# TLog_HighSpeedADC.net
KiCad netlist of a schematic drawn in EAGLE
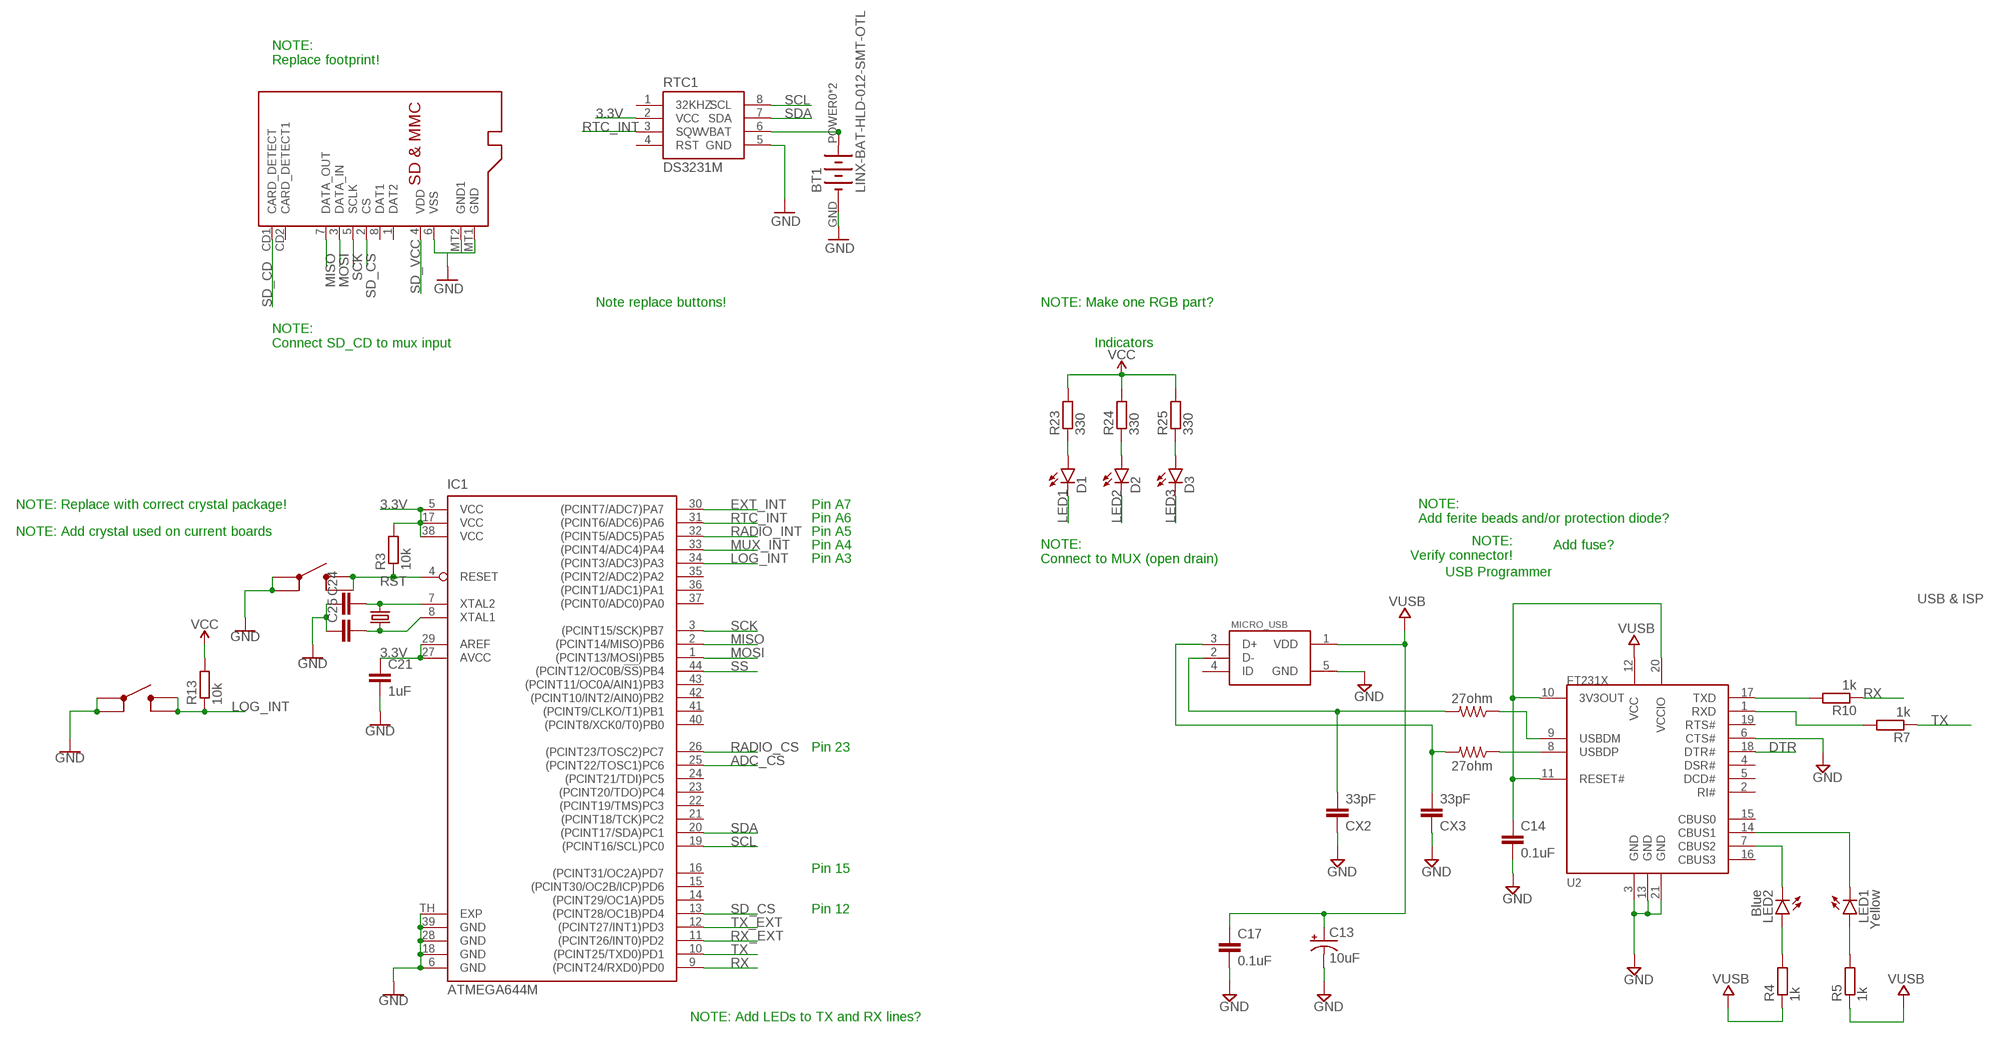
[diagram p0: schematic, sheet 1]
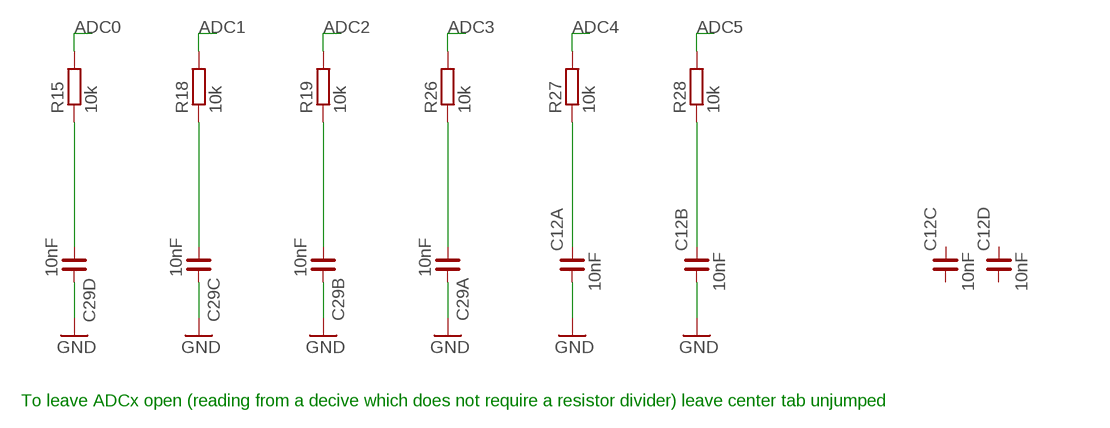
[diagram p1: schematic, sheet 2]
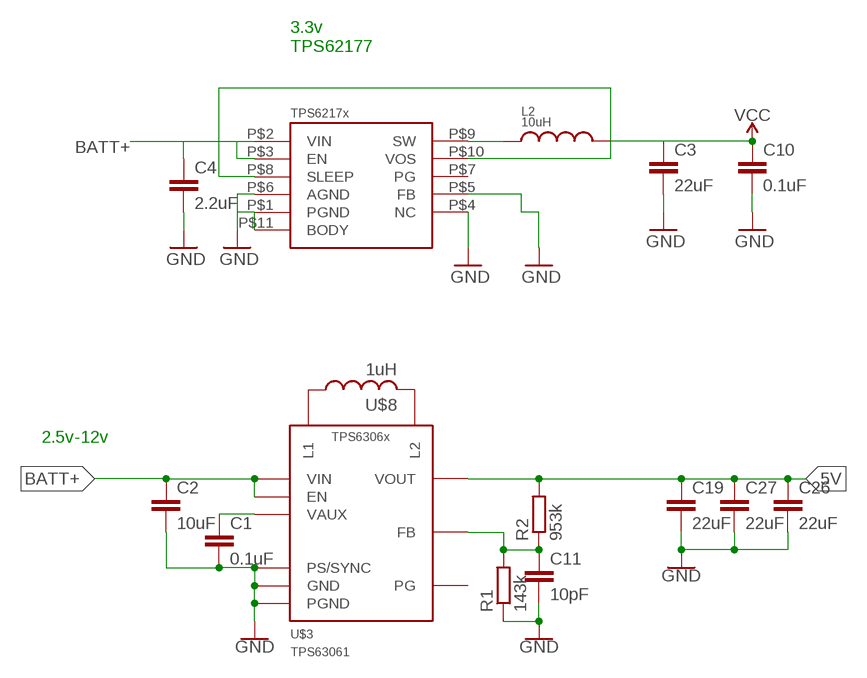
[diagram p2: schematic, sheet 3]
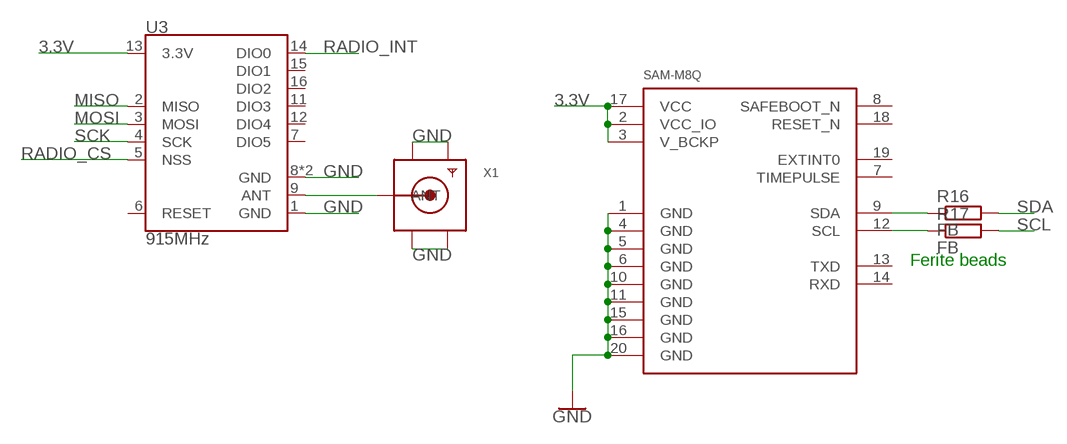
[diagram p3: schematic, sheet 4]
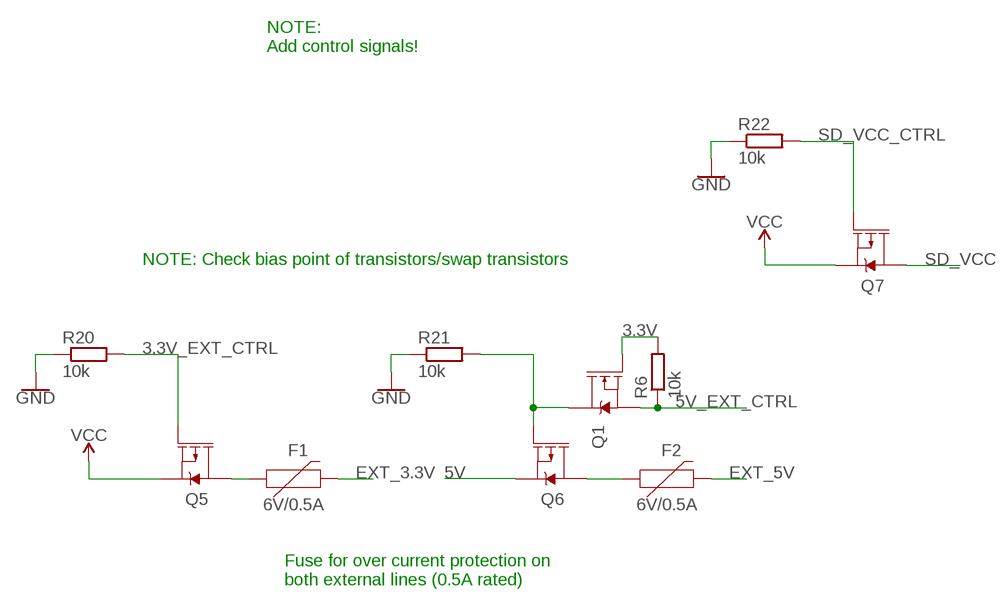
[diagram p4: schematic, sheet 5]
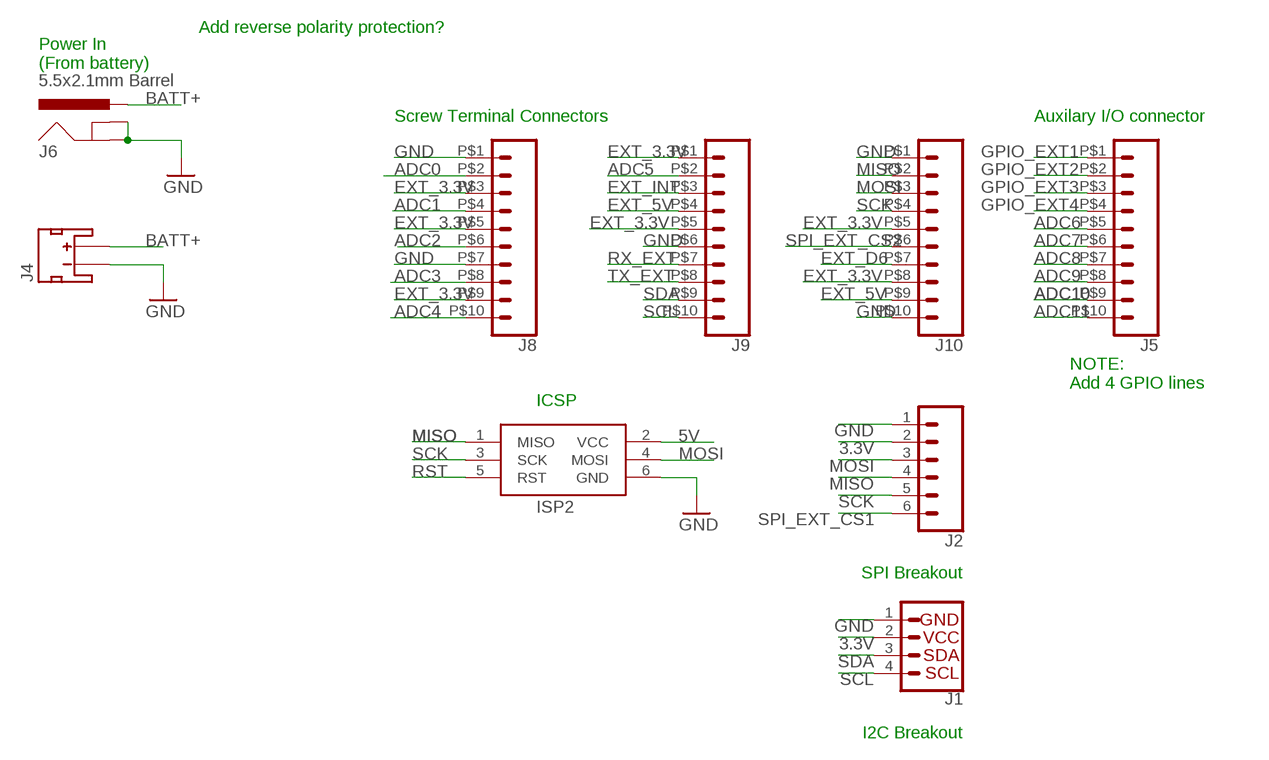
[diagram p5: schematic, sheet 6]
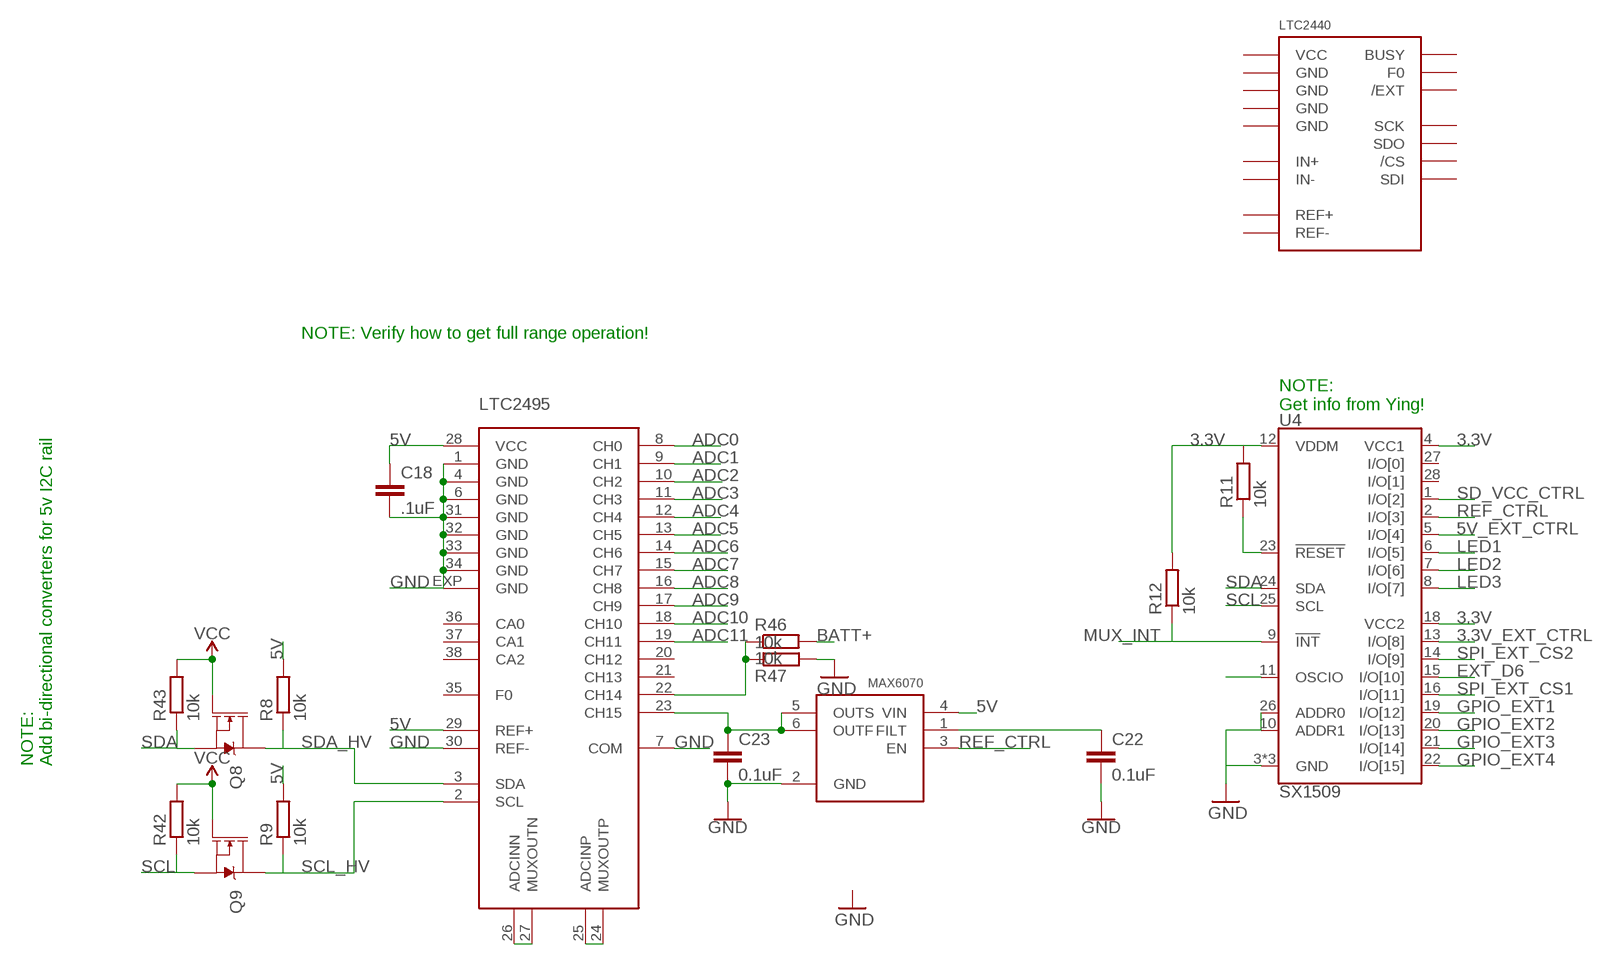
[diagram p6: schematic, sheet 7]

(export (version "E")
  (design (tool "Eeschema 10.0.6"))
  (components
    (comp (ref "R16")
      (value "FB")
      (footprint "eagle-import:R0603")
      (libsource (lib "eagle-import") (part "R-EU_R0603"))
    )
    (comp (ref "R17")
      (value "FB")
      (footprint "eagle-import:R0603")
      (libsource (lib "eagle-import") (part "R-EU_R0603"))
    )
    (comp (ref "U$6")
      (value "SAM-M8Q")
      (footprint "eagle-import:SAM-M8Q")
      (libsource (lib "eagle-import") (part "SAM-M8Q"))
    )
    (comp (ref "U3")
      (value "915MHz")
      (footprint "eagle-import:RFM69HCW-XXXS2")
      (libsource (lib "eagle-import") (part "RFM69HCW-915"))
    )
    (comp (ref "X1")
      (value "SMACONNECTOR_EDGE")
      (footprint "eagle-import:SMA_EDGELAUNCH")
      (libsource (lib "eagle-import") (part "SMACONNECTOR_EDGE"))
    )
    (comp (ref "C12")
      (value "10nF")
      (footprint "eagle-import:CECJ-1206")
      (libsource (lib "eagle-import") (part "CCA_ECJ-1206"))
    )
    (comp (ref "C29")
      (value "10nF")
      (footprint "eagle-import:CECJ-1206")
      (libsource (lib "eagle-import") (part "CCA_ECJ-1206"))
    )
    (comp (ref "R15")
      (value "10k")
      (footprint "eagle-import:R0603")
      (libsource (lib "eagle-import") (part "R-EU_R0603"))
    )
    (comp (ref "R18")
      (value "10k")
      (footprint "eagle-import:R0603")
      (libsource (lib "eagle-import") (part "R-EU_R0603"))
    )
    (comp (ref "R19")
      (value "10k")
      (footprint "eagle-import:R0603")
      (libsource (lib "eagle-import") (part "R-EU_R0603"))
    )
    (comp (ref "R26")
      (value "10k")
      (footprint "eagle-import:R0603")
      (libsource (lib "eagle-import") (part "R-EU_R0603"))
    )
    (comp (ref "R27")
      (value "10k")
      (footprint "eagle-import:R0603")
      (libsource (lib "eagle-import") (part "R-EU_R0603"))
    )
    (comp (ref "R28")
      (value "10k")
      (footprint "eagle-import:R0603")
      (libsource (lib "eagle-import") (part "R-EU_R0603"))
    )
    (comp (ref "C18")
      (value ".1uF")
      (footprint "eagle-import:C0603")
      (libsource (lib "eagle-import") (part "C-EUC0603"))
    )
    (comp (ref "C22")
      (value "0.1uF")
      (footprint "eagle-import:C0603")
      (libsource (lib "eagle-import") (part "C-EUC0603"))
    )
    (comp (ref "C23")
      (value "0.1uF")
      (footprint "eagle-import:C0603")
      (libsource (lib "eagle-import") (part "C-EUC0603"))
    )
    (comp (ref "Q8")
      (value "220mA/50V/3.5Ω")
      (footprint "eagle-import:SOT23-3")
      (libsource (lib "eagle-import") (part "MOSFET-NCH-BSS138"))
    )
    (comp (ref "Q9")
      (value "220mA/50V/3.5Ω")
      (footprint "eagle-import:SOT23-3")
      (libsource (lib "eagle-import") (part "MOSFET-NCH-BSS138"))
    )
    (comp (ref "R8")
      (value "10k")
      (footprint "eagle-import:R0603")
      (libsource (lib "eagle-import") (part "R-EU_R0603"))
    )
    (comp (ref "R9")
      (value "10k")
      (footprint "eagle-import:R0603")
      (libsource (lib "eagle-import") (part "R-EU_R0603"))
    )
    (comp (ref "R11")
      (value "10k")
      (footprint "eagle-import:R0603")
      (libsource (lib "eagle-import") (part "R-EU_R0603"))
    )
    (comp (ref "R12")
      (value "10k")
      (footprint "eagle-import:R0603")
      (libsource (lib "eagle-import") (part "R-EU_R0603"))
    )
    (comp (ref "R42")
      (value "10k")
      (footprint "eagle-import:R0603")
      (libsource (lib "eagle-import") (part "R-EU_R0603"))
    )
    (comp (ref "R43")
      (value "10k")
      (footprint "eagle-import:R0603")
      (libsource (lib "eagle-import") (part "R-EU_R0603"))
    )
    (comp (ref "R46")
      (value "10k")
      (footprint "eagle-import:R0603")
      (libsource (lib "eagle-import") (part "R-EU_R0603"))
    )
    (comp (ref "R47")
      (value "10k")
      (footprint "eagle-import:R0603")
      (libsource (lib "eagle-import") (part "R-EU_R0603"))
    )
    (comp (ref "U$7")
      (value "LTC2495")
      (footprint "eagle-import:QFN38-5X7")
      (libsource (lib "eagle-import") (part "LTC2495"))
    )
    (comp (ref "U$10")
      (value "MAX6070")
      (footprint "eagle-import:SOT23-6L")
      (libsource (lib "eagle-import") (part "MAX6070"))
    )
    (comp (ref "U$15")
      (value "LTC2440")
      (footprint "eagle-import:SSOP16")
      (libsource (lib "eagle-import") (part "LTC2440"))
    )
    (comp (ref "U4")
      (value "SX1509")
      (footprint "eagle-import:QFN-28")
      (libsource (lib "eagle-import") (part "SX1509"))
    )
    (comp (ref "BT1")
      (value "LINX-BAT-HLD-012-SMT-OTL")
      (footprint "eagle-import:LINX_BAT-HLD-012-SMT")
      (libsource (lib "eagle-import") (part "LINX-BAT-HLD-012-SMT-OTL"))
    )
    (comp (ref "C13")
      (value "10uF")
      (footprint "eagle-import:EIA3216")
      (libsource (lib "eagle-import") (part "CAP_POL1206"))
    )
    (comp (ref "C14")
      (value "0.1uF")
      (footprint "eagle-import:C0603")
      (libsource (lib "eagle-import") (part "resistor_C-EUC0603"))
    )
    (comp (ref "C17")
      (value "0.1uF")
      (footprint "eagle-import:C0603")
      (libsource (lib "eagle-import") (part "resistor_C-EUC0603"))
    )
    (comp (ref "C21")
      (value "1uF")
      (footprint "eagle-import:C0603")
      (libsource (lib "eagle-import") (part "C-EUC0603"))
    )
    (comp (ref "C24")
      (value "C-EUC0603")
      (footprint "eagle-import:C0603")
      (libsource (lib "eagle-import") (part "C-EUC0603"))
    )
    (comp (ref "C25")
      (value "C-EUC0603")
      (footprint "eagle-import:C0603")
      (libsource (lib "eagle-import") (part "C-EUC0603"))
    )
    (comp (ref "CX2")
      (value "33pF")
      (footprint "eagle-import:C0603")
      (libsource (lib "eagle-import") (part "resistor_C-EUC0603"))
    )
    (comp (ref "CX3")
      (value "33pF")
      (footprint "eagle-import:C0603")
      (libsource (lib "eagle-import") (part "resistor_C-EUC0603"))
    )
    (comp (ref "D+")
      (value "27ohm")
      (footprint "eagle-import:R0603")
      (libsource (lib "eagle-import") (part "R-US_R0603"))
    )
    (comp (ref "D-")
      (value "27ohm")
      (footprint "eagle-import:R0603")
      (libsource (lib "eagle-import") (part "R-US_R0603"))
    )
    (comp (ref "D1")
      (value "LED0603")
      (footprint "eagle-import:LED-0603")
      (libsource (lib "eagle-import") (part "LED0603"))
    )
    (comp (ref "D2")
      (value "LED0603")
      (footprint "eagle-import:LED-0603")
      (libsource (lib "eagle-import") (part "LED0603"))
    )
    (comp (ref "D3")
      (value "LED0603")
      (footprint "eagle-import:LED-0603")
      (libsource (lib "eagle-import") (part "LED0603"))
    )
    (comp (ref "IC1")
      (value "ATMEGA644M")
      (footprint "eagle-import:MLF44-TH")
      (fields (field (name "MPN") "ATMEGA644P-20MU"))
      (libsource (lib "eagle-import") (part "ATMEGA644M"))
    )
    (comp (ref "LED1")
      (value "Yellow")
      (footprint "eagle-import:LED-0603")
      (libsource (lib "eagle-import") (part "LED0603"))
    )
    (comp (ref "LED2")
      (value "Blue")
      (footprint "eagle-import:LED-0603")
      (libsource (lib "eagle-import") (part "LED0603"))
    )
    (comp (ref "MICRO_USB")
      (value "10118194-0001LF_LONGER_PADS")
      (footprint "eagle-import:10118194-0001LF_LONGER_PADS")
      (libsource (lib "eagle-import") (part "10118194-0001LF_LONGER_PADS"))
    )
    (comp (ref "R3")
      (value "10k")
      (footprint "eagle-import:R0603")
      (libsource (lib "eagle-import") (part "R-EU_R0603"))
    )
    (comp (ref "R4")
      (value "1k")
      (footprint "eagle-import:R0603")
      (libsource (lib "eagle-import") (part "rcl_334_R-EU_R0603"))
    )
    (comp (ref "R5")
      (value "1k")
      (footprint "eagle-import:R0603")
      (libsource (lib "eagle-import") (part "rcl_334_R-EU_R0603"))
    )
    (comp (ref "R7")
      (value "1k")
      (footprint "eagle-import:R0603")
      (libsource (lib "eagle-import") (part "rcl_334_R-EU_R0603"))
    )
    (comp (ref "R10")
      (value "1k")
      (footprint "eagle-import:R0603")
      (libsource (lib "eagle-import") (part "rcl_334_R-EU_R0603"))
    )
    (comp (ref "R13")
      (value "10k")
      (footprint "eagle-import:R0603")
      (libsource (lib "eagle-import") (part "resistor_R-EU_R0603"))
    )
    (comp (ref "R23")
      (value "330")
      (footprint "eagle-import:R0603")
      (libsource (lib "eagle-import") (part "R-EU_R0603"))
    )
    (comp (ref "R24")
      (value "330")
      (footprint "eagle-import:R0603")
      (libsource (lib "eagle-import") (part "R-EU_R0603"))
    )
    (comp (ref "R25")
      (value "330")
      (footprint "eagle-import:R0603")
      (libsource (lib "eagle-import") (part "R-EU_R0603"))
    )
    (comp (ref "RTC1")
      (value "DS3231M")
      (footprint "eagle-import:SO08")
      (libsource (lib "eagle-import") (part "DS3231M"))
    )
    (comp (ref "U$1")
      (value "CRYSTAL_5X3.2_2LEAD")
      (footprint "eagle-import:CRYSTAL_5X3.2_2-SMD")
      (libsource (lib "eagle-import") (part "CRYSTAL_5X3.2_2LEAD"))
    )
    (comp (ref "U$2")
      (value "MICROSD")
      (footprint "eagle-import:MICROSD")
      (libsource (lib "eagle-import") (part "MICROSD"))
    )
    (comp (ref "U$5")
      (value "SKRPABE010")
      (footprint "eagle-import:SKRPABE010_(SWITCH)")
      (libsource (lib "eagle-import") (part "SKRPABE010"))
    )
    (comp (ref "U$9")
      (value "SKRPABE010")
      (footprint "eagle-import:SKRPABE010_(SWITCH)")
      (libsource (lib "eagle-import") (part "SKRPABE010"))
    )
    (comp (ref "U2")
      (value "FT231X-Q")
      (footprint "eagle-import:QFN20")
      (libsource (lib "eagle-import") (part "FT231X-Q"))
    )
    (comp (ref "F1")
      (value "6V/0.5A")
      (footprint "eagle-import:1206")
      (libsource (lib "eagle-import") (part "PPTC_HALF-AMP"))
    )
    (comp (ref "F2")
      (value "6V/0.5A")
      (footprint "eagle-import:1206")
      (libsource (lib "eagle-import") (part "PPTC_HALF-AMP"))
    )
    (comp (ref "Q1")
      (value "220mA/50V/3.5Ω")
      (footprint "eagle-import:SOT23-3")
      (libsource (lib "eagle-import") (part "MOSFET-NCH-BSS138"))
    )
    (comp (ref "Q5")
      (value "4.3A/20V/54mΩ")
      (footprint "eagle-import:SOT23-3")
      (libsource (lib "eagle-import") (part "MOSFET_PCH-IRLML2244"))
    )
    (comp (ref "Q6")
      (value "4.3A/20V/54mΩ")
      (footprint "eagle-import:SOT23-3")
      (libsource (lib "eagle-import") (part "MOSFET_PCH-IRLML2244"))
    )
    (comp (ref "Q7")
      (value "4.3A/20V/54mΩ")
      (footprint "eagle-import:SOT23-3")
      (libsource (lib "eagle-import") (part "MOSFET_PCH-IRLML2244"))
    )
    (comp (ref "R6")
      (value "10k")
      (footprint "eagle-import:R0603")
      (libsource (lib "eagle-import") (part "resistor_R-EU_R0603"))
    )
    (comp (ref "R20")
      (value "10k")
      (footprint "eagle-import:R0603")
      (libsource (lib "eagle-import") (part "R-EU_R0603"))
    )
    (comp (ref "R21")
      (value "10k")
      (footprint "eagle-import:R0603")
      (libsource (lib "eagle-import") (part "R-EU_R0603"))
    )
    (comp (ref "R22")
      (value "10k")
      (footprint "eagle-import:R0603")
      (libsource (lib "eagle-import") (part "R-EU_R0603"))
    )
    (comp (ref "C1")
      (value "0.1uF")
      (footprint "eagle-import:C0603")
      (libsource (lib "eagle-import") (part "C-EUC0603"))
    )
    (comp (ref "C2")
      (value "10uF")
      (footprint "eagle-import:C0603")
      (libsource (lib "eagle-import") (part "C-EUC0603"))
    )
    (comp (ref "C3")
      (value "22uF")
      (footprint "eagle-import:C1210")
      (libsource (lib "eagle-import") (part "C-EUC1210"))
    )
    (comp (ref "C4")
      (value "2.2uF")
      (footprint "eagle-import:C0603")
      (libsource (lib "eagle-import") (part "C-EUC0603"))
    )
    (comp (ref "C10")
      (value "0.1uF")
      (footprint "eagle-import:C0603")
      (libsource (lib "eagle-import") (part "C-EUC0603"))
    )
    (comp (ref "C11")
      (value "10pF")
      (footprint "eagle-import:C0603")
      (libsource (lib "eagle-import") (part "C-EUC0603"))
    )
    (comp (ref "C19")
      (value "22uF")
      (footprint "eagle-import:C0603")
      (libsource (lib "eagle-import") (part "C-EUC0603"))
    )
    (comp (ref "C26")
      (value "22uF")
      (footprint "eagle-import:C0603")
      (libsource (lib "eagle-import") (part "C-EUC0603"))
    )
    (comp (ref "C27")
      (value "22uF")
      (footprint "eagle-import:C0603")
      (libsource (lib "eagle-import") (part "C-EUC0603"))
    )
    (comp (ref "L2")
      (value "10uH")
      (footprint "eagle-import:WE-LQS(INDUCTOR)")
      (libsource (lib "eagle-import") (part "WE-LSQ(INDUCTOR)"))
    )
    (comp (ref "R1")
      (value "143k")
      (footprint "eagle-import:R0603")
      (libsource (lib "eagle-import") (part "R-EU_R0603"))
    )
    (comp (ref "R2")
      (value "953k")
      (footprint "eagle-import:R0603")
      (libsource (lib "eagle-import") (part "R-EU_R0603"))
    )
    (comp (ref "U$3")
      (value "TPS63061")
      (footprint "eagle-import:WSON-10")
      (libsource (lib "eagle-import") (part "TPS306X"))
    )
    (comp (ref "U$4")
      (value "TPS6217X")
      (footprint "eagle-import:WSON-10")
      (libsource (lib "eagle-import") (part "TPS6217X"))
    )
    (comp (ref "U$8")
      (value "1uH")
      (footprint "eagle-import:WE-MAIA(4.1X4.1)")
      (libsource (lib "eagle-import") (part "WE-MAIA(INDUCTOR)"))
    )
    (comp (ref "ISP2")
      (value "AVRISP-6")
      (footprint "eagle-import:AVRISP")
      (libsource (lib "eagle-import") (part "AVRISP-6"))
    )
    (comp (ref "J1")
      (value "I2C_STANDARD")
      (footprint "eagle-import:1X04")
      (libsource (lib "eagle-import") (part "I2C_STANDARD"))
    )
    (comp (ref "J2")
      (value "CONN_06SILK_FEMALE_PTH")
      (footprint "eagle-import:1X06")
      (libsource (lib "eagle-import") (part "CONN_06SILK_FEMALE_PTH"))
    )
    (comp (ref "J4")
      (value "JST_2MM_MALE")
      (footprint "eagle-import:JST-2-SMD")
      (libsource (lib "eagle-import") (part "JST_2MM_MALE"))
    )
    (comp (ref "J5")
      (value "CONN_10")
      (footprint "eagle-import:SCREWTERMINAL-3.5MM-10")
      (libsource (lib "eagle-import") (part "CONN_10"))
    )
    (comp (ref "J6")
      (value "5.5x2.1mm Barrel")
      (footprint "eagle-import:POWER_JACK_SMD")
      (libsource (lib "eagle-import") (part "POWER_JACKSMD"))
    )
    (comp (ref "J8")
      (value "CONN_10")
      (footprint "eagle-import:SCREWTERMINAL-3.5MM-10")
      (libsource (lib "eagle-import") (part "CONN_10"))
    )
    (comp (ref "J9")
      (value "CONN_10")
      (footprint "eagle-import:SCREWTERMINAL-3.5MM-10")
      (libsource (lib "eagle-import") (part "CONN_10"))
    )
    (comp (ref "J10")
      (value "CONN_10")
      (footprint "eagle-import:SCREWTERMINAL-3.5MM-10")
      (libsource (lib "eagle-import") (part "CONN_10"))
    )
  )
  (nets
    (net (code "1") (name "3.3V") (class "Default")
      (node (ref "C10") (pin "1") (pinfunction "1_1") (pintype "passive"))
      (node (ref "C21") (pin "1") (pinfunction "1_1") (pintype "passive"))
      (node (ref "C3") (pin "1") (pinfunction "1_1") (pintype "passive"))
      (node (ref "IC1") (pin "17") (pinfunction "VCC_17") (pintype "power_in"))
      (node (ref "IC1") (pin "27") (pinfunction "AVCC_27") (pintype "power_in"))
      (node (ref "IC1") (pin "29") (pinfunction "AREF_29") (pintype "passive"))
      (node (ref "IC1") (pin "38") (pinfunction "VCC_38") (pintype "power_in"))
      (node (ref "IC1") (pin "5") (pinfunction "VCC_5") (pintype "power_in"))
      (node (ref "J1") (pin "2") (pinfunction "2_2") (pintype "power_in"))
      (node (ref "J2") (pin "2") (pinfunction "2_2") (pintype "passive"))
      (node (ref "L2") (pin "P$2") (pinfunction "P$2_P$2") (pintype "bidirectional"))
      (node (ref "Q1") (pin "1") (pinfunction "G_1") (pintype "bidirectional"))
      (node (ref "Q5") (pin "2") (pinfunction "S_2") (pintype "bidirectional"))
      (node (ref "Q7") (pin "2") (pinfunction "S_2") (pintype "bidirectional"))
      (node (ref "Q8") (pin "1") (pinfunction "G_1") (pintype "bidirectional"))
      (node (ref "Q9") (pin "1") (pinfunction "G_1") (pintype "bidirectional"))
      (node (ref "R11") (pin "2") (pinfunction "2_2") (pintype "passive"))
      (node (ref "R12") (pin "2") (pinfunction "2_2") (pintype "passive"))
      (node (ref "R13") (pin "2") (pinfunction "2_2") (pintype "passive"))
      (node (ref "R23") (pin "2") (pinfunction "2_2") (pintype "passive"))
      (node (ref "R24") (pin "2") (pinfunction "2_2") (pintype "passive"))
      (node (ref "R25") (pin "2") (pinfunction "2_2") (pintype "passive"))
      (node (ref "R3") (pin "2") (pinfunction "2_2") (pintype "passive"))
      (node (ref "R42") (pin "2") (pinfunction "2_2") (pintype "passive"))
      (node (ref "R43") (pin "2") (pinfunction "2_2") (pintype "passive"))
      (node (ref "R6") (pin "2") (pinfunction "2_2") (pintype "passive"))
      (node (ref "RTC1") (pin "2") (pinfunction "VCC_2") (pintype "power_in"))
      (node (ref "U$4") (pin "P$10") (pinfunction "VOS_P$10") (pintype "bidirectional"))
      (node (ref "U$4") (pin "P$8") (pinfunction "SLEEP_P$8") (pintype "bidirectional"))
      (node (ref "U$6") (pin "17") (pinfunction "VCC_17") (pintype "bidirectional"))
      (node (ref "U$6") (pin "2") (pinfunction "VCC_IO_2") (pintype "bidirectional"))
      (node (ref "U$6") (pin "3") (pinfunction "V_BCKP_3") (pintype "bidirectional"))
      (node (ref "U3") (pin "13") (pinfunction "3.3V_13") (pintype "power_in"))
      (node (ref "U4") (pin "12") (pinfunction "VDDM_12") (pintype "bidirectional"))
      (node (ref "U4") (pin "18") (pinfunction "VCC2_18") (pintype "bidirectional"))
      (node (ref "U4") (pin "4") (pinfunction "VCC1_4") (pintype "bidirectional"))
    )
    (net (code "2") (name "3.3V_EXT_CTRL") (class "Default")
      (node (ref "Q5") (pin "1") (pinfunction "G_1") (pintype "bidirectional"))
      (node (ref "R20") (pin "2") (pinfunction "2_2") (pintype "passive"))
      (node (ref "U4") (pin "13") (pinfunction "I/O[8]_13") (pintype "bidirectional"))
    )
    (net (code "3") (name "5V") (class "Default")
      (node (ref "C18") (pin "1") (pinfunction "1_1") (pintype "passive"))
      (node (ref "C19") (pin "1") (pinfunction "1_1") (pintype "passive"))
      (node (ref "C26") (pin "1") (pinfunction "1_1") (pintype "passive"))
      (node (ref "C27") (pin "1") (pinfunction "1_1") (pintype "passive"))
      (node (ref "ISP2") (pin "2") (pinfunction "VCC_2") (pintype "power_in"))
      (node (ref "Q6") (pin "2") (pinfunction "S_2") (pintype "bidirectional"))
      (node (ref "R2") (pin "2") (pinfunction "2_2") (pintype "passive"))
      (node (ref "R8") (pin "2") (pinfunction "2_2") (pintype "passive"))
      (node (ref "R9") (pin "2") (pinfunction "2_2") (pintype "passive"))
      (node (ref "U$10") (pin "4") (pinfunction "VIN_4") (pintype "bidirectional"))
      (node (ref "U$3") (pin "P$9") (pinfunction "VOUT_P$9") (pintype "input"))
      (node (ref "U$7") (pin "28") (pinfunction "VCC_28") (pintype "power_in"))
      (node (ref "U$7") (pin "29") (pinfunction "REF+_29") (pintype "input"))
    )
    (net (code "4") (name "5V_EXT_CTRL") (class "Default")
      (node (ref "Q1") (pin "2") (pinfunction "S_2") (pintype "bidirectional"))
      (node (ref "R6") (pin "1") (pinfunction "1_1") (pintype "passive"))
      (node (ref "U4") (pin "5") (pinfunction "I/O[4]_5") (pintype "bidirectional"))
    )
    (net (code "5") (name "ADC0") (class "Default")
      (node (ref "J8") (pin "P$2") (pinfunction "2_P$2") (pintype "passive"))
      (node (ref "R15") (pin "2") (pinfunction "2_2") (pintype "passive"))
      (node (ref "U$7") (pin "8") (pinfunction "CH0_8") (pintype "input"))
    )
    (net (code "6") (name "ADC1") (class "Default")
      (node (ref "J8") (pin "P$4") (pinfunction "4_P$4") (pintype "passive"))
      (node (ref "R18") (pin "2") (pinfunction "2_2") (pintype "passive"))
      (node (ref "U$7") (pin "9") (pinfunction "CH1_9") (pintype "input"))
    )
    (net (code "7") (name "ADC2") (class "Default")
      (node (ref "J8") (pin "P$6") (pinfunction "6_P$6") (pintype "passive"))
      (node (ref "R19") (pin "2") (pinfunction "2_2") (pintype "passive"))
      (node (ref "U$7") (pin "10") (pinfunction "CH2_10") (pintype "input"))
    )
    (net (code "8") (name "ADC3") (class "Default")
      (node (ref "J8") (pin "P$8") (pinfunction "8_P$8") (pintype "passive"))
      (node (ref "R26") (pin "2") (pinfunction "2_2") (pintype "passive"))
      (node (ref "U$7") (pin "11") (pinfunction "CH3_11") (pintype "input"))
    )
    (net (code "9") (name "ADC4") (class "Default")
      (node (ref "J8") (pin "P$10") (pinfunction "10_P$10") (pintype "passive"))
      (node (ref "R27") (pin "2") (pinfunction "2_2") (pintype "passive"))
      (node (ref "U$7") (pin "12") (pinfunction "CH4_12") (pintype "input"))
    )
    (net (code "10") (name "ADC5") (class "Default")
      (node (ref "J9") (pin "P$2") (pinfunction "2_P$2") (pintype "passive"))
      (node (ref "R28") (pin "2") (pinfunction "2_2") (pintype "passive"))
      (node (ref "U$7") (pin "13") (pinfunction "CH5_13") (pintype "input"))
    )
    (net (code "11") (name "ADC6") (class "Default")
      (node (ref "J5") (pin "P$5") (pinfunction "5_P$5") (pintype "passive"))
      (node (ref "U$7") (pin "14") (pinfunction "CH6_14") (pintype "input"))
    )
    (net (code "12") (name "ADC7") (class "Default")
      (node (ref "J5") (pin "P$6") (pinfunction "6_P$6") (pintype "passive"))
      (node (ref "U$7") (pin "15") (pinfunction "CH7_15") (pintype "input"))
    )
    (net (code "13") (name "ADC8") (class "Default")
      (node (ref "J5") (pin "P$7") (pinfunction "7_P$7") (pintype "passive"))
      (node (ref "U$7") (pin "16") (pinfunction "CH8_16") (pintype "input"))
    )
    (net (code "14") (name "ADC9") (class "Default")
      (node (ref "J5") (pin "P$8") (pinfunction "8_P$8") (pintype "passive"))
      (node (ref "U$7") (pin "17") (pinfunction "CH9_17") (pintype "input"))
    )
    (net (code "15") (name "ADC10") (class "Default")
      (node (ref "J5") (pin "P$9") (pinfunction "9_P$9") (pintype "passive"))
      (node (ref "U$7") (pin "18") (pinfunction "CH10_18") (pintype "input"))
    )
    (net (code "16") (name "ADC11") (class "Default")
      (node (ref "J5") (pin "P$10") (pinfunction "10_P$10") (pintype "passive"))
      (node (ref "U$7") (pin "19") (pinfunction "CH11_19") (pintype "input"))
    )
    (net (code "17") (name "ADC_CS") (class "Default")
      (node (ref "IC1") (pin "25") (pinfunction "(PCINT22/TOSC1)PC6_25") (pintype "output"))
    )
    (net (code "18") (name "BATT+") (class "Default")
      (node (ref "C2") (pin "1") (pinfunction "1_1") (pintype "passive"))
      (node (ref "C4") (pin "1") (pinfunction "1_1") (pintype "passive"))
      (node (ref "J4") (pin "2") (pinfunction "+_2") (pintype "bidirectional"))
      (node (ref "J6") (pin "VIN0") (pinfunction "PWR_VIN0") (pintype "bidirectional"))
      (node (ref "R46") (pin "2") (pinfunction "2_2") (pintype "passive"))
      (node (ref "U$3") (pin "P$2") (pinfunction "VIN_P$2") (pintype "input"))
      (node (ref "U$3") (pin "P$3") (pinfunction "EN_P$3") (pintype "input"))
      (node (ref "U$4") (pin "P$2") (pinfunction "VIN_P$2") (pintype "bidirectional"))
      (node (ref "U$4") (pin "P$3") (pinfunction "EN_P$3") (pintype "bidirectional"))
    )
    (net (code "19") (name "DTR") (class "Default")
      (node (ref "U2") (pin "18") (pinfunction "DTR#_18") (pintype "bidirectional"))
    )
    (net (code "20") (name "EXT_3.3V") (class "Default")
      (node (ref "F1") (pin "2") (pinfunction "2_2") (pintype "bidirectional"))
      (node (ref "J10") (pin "P$5") (pinfunction "5_P$5") (pintype "passive"))
      (node (ref "J10") (pin "P$8") (pinfunction "8_P$8") (pintype "passive"))
      (node (ref "J8") (pin "P$3") (pinfunction "3_P$3") (pintype "passive"))
      (node (ref "J8") (pin "P$5") (pinfunction "5_P$5") (pintype "passive"))
      (node (ref "J8") (pin "P$9") (pinfunction "9_P$9") (pintype "passive"))
      (node (ref "J9") (pin "P$1") (pinfunction "1_P$1") (pintype "passive"))
      (node (ref "J9") (pin "P$5") (pinfunction "5_P$5") (pintype "passive"))
    )
    (net (code "21") (name "EXT_5V") (class "Default")
      (node (ref "F2") (pin "2") (pinfunction "2_2") (pintype "bidirectional"))
      (node (ref "J10") (pin "P$9") (pinfunction "9_P$9") (pintype "passive"))
      (node (ref "J9") (pin "P$4") (pinfunction "4_P$4") (pintype "passive"))
    )
    (net (code "22") (name "EXT_D6") (class "Default")
      (node (ref "J10") (pin "P$7") (pinfunction "7_P$7") (pintype "passive"))
      (node (ref "U4") (pin "15") (pinfunction "I/O[10]_15") (pintype "bidirectional"))
    )
    (net (code "23") (name "EXT_INT") (class "Default")
      (node (ref "IC1") (pin "30") (pinfunction "(PCINT7/ADC7)PA7_30") (pintype "bidirectional"))
      (node (ref "J9") (pin "P$3") (pinfunction "3_P$3") (pintype "passive"))
    )
    (net (code "24") (name "GND") (class "Default")
      (node (ref "BT1") (pin "GND") (pinfunction "-_GND") (pintype "passive"))
      (node (ref "C1") (pin "2") (pinfunction "2_2") (pintype "passive"))
      (node (ref "C10") (pin "2") (pinfunction "2_2") (pintype "passive"))
      (node (ref "C11") (pin "2") (pinfunction "2_2") (pintype "passive"))
      (node (ref "C12") (pin "A1") (pinfunction "1_A1") (pintype "passive"))
      (node (ref "C12") (pin "B1") (pinfunction "1_B1") (pintype "passive"))
      (node (ref "C13") (pin "C") (pinfunction "-_C") (pintype "passive"))
      (node (ref "C14") (pin "2") (pinfunction "2_2") (pintype "passive"))
      (node (ref "C17") (pin "2") (pinfunction "2_2") (pintype "passive"))
      (node (ref "C18") (pin "2") (pinfunction "2_2") (pintype "passive"))
      (node (ref "C19") (pin "2") (pinfunction "2_2") (pintype "passive"))
      (node (ref "C2") (pin "2") (pinfunction "2_2") (pintype "passive"))
      (node (ref "C21") (pin "2") (pinfunction "2_2") (pintype "passive"))
      (node (ref "C22") (pin "2") (pinfunction "2_2") (pintype "passive"))
      (node (ref "C23") (pin "2") (pinfunction "2_2") (pintype "passive"))
      (node (ref "C24") (pin "1") (pinfunction "1_1") (pintype "passive"))
      (node (ref "C25") (pin "1") (pinfunction "1_1") (pintype "passive"))
      (node (ref "C26") (pin "2") (pinfunction "2_2") (pintype "passive"))
      (node (ref "C27") (pin "2") (pinfunction "2_2") (pintype "passive"))
      (node (ref "C29") (pin "A2") (pinfunction "2_A2") (pintype "passive"))
      (node (ref "C29") (pin "B2") (pinfunction "2_B2") (pintype "passive"))
      (node (ref "C29") (pin "C2") (pinfunction "2_C2") (pintype "passive"))
      (node (ref "C29") (pin "D2") (pinfunction "2_D2") (pintype "passive"))
      (node (ref "C3") (pin "2") (pinfunction "2_2") (pintype "passive"))
      (node (ref "C4") (pin "2") (pinfunction "2_2") (pintype "passive"))
      (node (ref "CX2") (pin "1") (pinfunction "1_1") (pintype "passive"))
      (node (ref "CX3") (pin "1") (pinfunction "1_1") (pintype "passive"))
      (node (ref "IC1") (pin "18") (pinfunction "GND_18") (pintype "power_in"))
      (node (ref "IC1") (pin "28") (pinfunction "GND_28") (pintype "power_in"))
      (node (ref "IC1") (pin "39") (pinfunction "GND_39") (pintype "power_in"))
      (node (ref "IC1") (pin "6") (pinfunction "GND_6") (pintype "power_in"))
      (node (ref "IC1") (pin "TH") (pinfunction "EXP_TH") (pintype "power_in"))
      (node (ref "ISP2") (pin "6") (pinfunction "GND_6") (pintype "power_in"))
      (node (ref "J1") (pin "1") (pinfunction "1_1") (pintype "power_in"))
      (node (ref "J10") (pin "P$1") (pinfunction "1_P$1") (pintype "passive"))
      (node (ref "J10") (pin "P$10") (pinfunction "10_P$10") (pintype "passive"))
      (node (ref "J2") (pin "1") (pinfunction "1_1") (pintype "passive"))
      (node (ref "J4") (pin "1") (pinfunction "-_1") (pintype "bidirectional"))
      (node (ref "J6") (pin "GND") (pinfunction "GNDBREAK_GND") (pintype "bidirectional"))
      (node (ref "J6") (pin "P$4") (pinfunction "GND_P$4") (pintype "bidirectional"))
      (node (ref "J8") (pin "P$1") (pinfunction "1_P$1") (pintype "passive"))
      (node (ref "J8") (pin "P$7") (pinfunction "7_P$7") (pintype "passive"))
      (node (ref "J9") (pin "P$6") (pinfunction "6_P$6") (pintype "passive"))
      (node (ref "MICRO_USB") (pin "5") (pinfunction "GND_5") (pintype "power_in"))
      (node (ref "R1") (pin "1") (pinfunction "1_1") (pintype "passive"))
      (node (ref "R20") (pin "1") (pinfunction "1_1") (pintype "passive"))
      (node (ref "R21") (pin "1") (pinfunction "1_1") (pintype "passive"))
      (node (ref "R22") (pin "1") (pinfunction "1_1") (pintype "passive"))
      (node (ref "R47") (pin "2") (pinfunction "2_2") (pintype "passive"))
      (node (ref "RTC1") (pin "5") (pinfunction "GND_5") (pintype "power_in"))
      (node (ref "U$10") (pin "2") (pinfunction "GND_2") (pintype "bidirectional"))
      (node (ref "U$2") (pin "6") (pinfunction "VSS_6") (pintype "power_in"))
      (node (ref "U$2") (pin "MT1") (pinfunction "GND_MT1") (pintype "power_in"))
      (node (ref "U$2") (pin "MT2") (pinfunction "GND1_MT2") (pintype "power_in"))
      (node (ref "U$3") (pin "P$11") (pinfunction "PGND_P$11") (pintype "input"))
      (node (ref "U$3") (pin "P$4") (pinfunction "PS/SYNC_P$4") (pintype "input"))
      (node (ref "U$3") (pin "P$7") (pinfunction "GND_P$7") (pintype "input"))
      (node (ref "U$4") (pin "P$1") (pinfunction "PGND_P$1") (pintype "bidirectional"))
      (node (ref "U$4") (pin "P$11") (pinfunction "BODY_P$11") (pintype "bidirectional"))
      (node (ref "U$4") (pin "P$4") (pinfunction "NC_P$4") (pintype "bidirectional"))
      (node (ref "U$4") (pin "P$5") (pinfunction "FB_P$5") (pintype "bidirectional"))
      (node (ref "U$4") (pin "P$6") (pinfunction "AGND_P$6") (pintype "bidirectional"))
      (node (ref "U$5") (pin "P$1") (pinfunction "1_P$1") (pintype "bidirectional"))
      (node (ref "U$5") (pin "P$2") (pinfunction "2_P$2") (pintype "bidirectional"))
      (node (ref "U$6") (pin "1") (pinfunction "GND_1") (pintype "bidirectional"))
      (node (ref "U$6") (pin "10") (pinfunction "GND_10") (pintype "bidirectional"))
      (node (ref "U$6") (pin "11") (pinfunction "GND_11") (pintype "bidirectional"))
      (node (ref "U$6") (pin "15") (pinfunction "GND_15") (pintype "bidirectional"))
      (node (ref "U$6") (pin "16") (pinfunction "GND_16") (pintype "bidirectional"))
      (node (ref "U$6") (pin "20") (pinfunction "GND_20") (pintype "bidirectional"))
      (node (ref "U$6") (pin "4") (pinfunction "GND_4") (pintype "bidirectional"))
      (node (ref "U$6") (pin "5") (pinfunction "GND_5") (pintype "bidirectional"))
      (node (ref "U$6") (pin "6") (pinfunction "GND_6") (pintype "bidirectional"))
      (node (ref "U$7") (pin "1") (pinfunction "GND_1") (pintype "power_in"))
      (node (ref "U$7") (pin "30") (pinfunction "REF-_30") (pintype "input"))
      (node (ref "U$7") (pin "31") (pinfunction "GND_31") (pintype "power_in"))
      (node (ref "U$7") (pin "32") (pinfunction "GND_32") (pintype "power_in"))
      (node (ref "U$7") (pin "33") (pinfunction "GND_33") (pintype "power_in"))
      (node (ref "U$7") (pin "34") (pinfunction "GND_34") (pintype "power_in"))
      (node (ref "U$7") (pin "4") (pinfunction "GND_4") (pintype "power_in"))
      (node (ref "U$7") (pin "6") (pinfunction "GND_6") (pintype "power_in"))
      (node (ref "U$7") (pin "7") (pinfunction "COM_7") (pintype "input"))
      (node (ref "U$7") (pin "EXP") (pinfunction "GND_EXP") (pintype "power_in"))
      (node (ref "U$9") (pin "P$1") (pinfunction "1_P$1") (pintype "bidirectional"))
      (node (ref "U$9") (pin "P$2") (pinfunction "2_P$2") (pintype "bidirectional"))
      (node (ref "U2") (pin "13") (pinfunction "GND_13") (pintype "bidirectional"))
      (node (ref "U2") (pin "21") (pinfunction "GND_21") (pintype "bidirectional"))
      (node (ref "U2") (pin "3") (pinfunction "GND_3") (pintype "bidirectional"))
      (node (ref "U2") (pin "6") (pinfunction "CTS#_6") (pintype "bidirectional"))
      (node (ref "U3") (pin "1") (pinfunction "GND_1") (pintype "power_in"))
      (node (ref "U3") (pin "10") (pinfunction "GND_10") (pintype "power_in"))
      (node (ref "U3") (pin "8") (pinfunction "GND_8") (pintype "power_in"))
      (node (ref "U4") (pin "10") (pinfunction "ADDR1_10") (pintype "bidirectional"))
      (node (ref "U4") (pin "17") (pinfunction "GND_17") (pintype "bidirectional"))
      (node (ref "U4") (pin "26") (pinfunction "ADDR0_26") (pintype "bidirectional"))
      (node (ref "U4") (pin "29") (pinfunction "GND_29") (pintype "bidirectional"))
      (node (ref "U4") (pin "3") (pinfunction "GND_3") (pintype "bidirectional"))
      (node (ref "X1") (pin "GND@1") (pinfunction "GND4_GND@1") (pintype "power_in"))
      (node (ref "X1") (pin "GND@2") (pinfunction "GND3_GND@2") (pintype "power_in"))
      (node (ref "X1") (pin "GND@3") (pinfunction "GND2_GND@3") (pintype "power_in"))
      (node (ref "X1") (pin "GND@4") (pinfunction "GND1_GND@4") (pintype "power_in"))
    )
    (net (code "25") (name "GPIO_EXT1") (class "Default")
      (node (ref "J5") (pin "P$1") (pinfunction "1_P$1") (pintype "passive"))
      (node (ref "U4") (pin "19") (pinfunction "I/O[12]_19") (pintype "bidirectional"))
    )
    (net (code "26") (name "GPIO_EXT2") (class "Default")
      (node (ref "J5") (pin "P$2") (pinfunction "2_P$2") (pintype "passive"))
      (node (ref "U4") (pin "20") (pinfunction "I/O[13]_20") (pintype "bidirectional"))
    )
    (net (code "27") (name "GPIO_EXT3") (class "Default")
      (node (ref "J5") (pin "P$3") (pinfunction "3_P$3") (pintype "passive"))
      (node (ref "U4") (pin "21") (pinfunction "I/O[14]_21") (pintype "bidirectional"))
    )
    (net (code "28") (name "GPIO_EXT4") (class "Default")
      (node (ref "J5") (pin "P$4") (pinfunction "4_P$4") (pintype "passive"))
      (node (ref "U4") (pin "22") (pinfunction "I/O[15]_22") (pintype "bidirectional"))
    )
    (net (code "29") (name "LED1") (class "Default")
      (node (ref "D1") (pin "C") (pinfunction "C_C") (pintype "passive"))
      (node (ref "U4") (pin "6") (pinfunction "I/O[5]_6") (pintype "bidirectional"))
    )
    (net (code "30") (name "LED2") (class "Default")
      (node (ref "D2") (pin "C") (pinfunction "C_C") (pintype "passive"))
      (node (ref "U4") (pin "7") (pinfunction "I/O[6]_7") (pintype "bidirectional"))
    )
    (net (code "31") (name "LED3") (class "Default")
      (node (ref "D3") (pin "C") (pinfunction "C_C") (pintype "passive"))
      (node (ref "U4") (pin "8") (pinfunction "I/O[7]_8") (pintype "bidirectional"))
    )
    (net (code "32") (name "LOG_INT") (class "Default")
      (node (ref "IC1") (pin "34") (pinfunction "(PCINT3/ADC3)PA3_34") (pintype "bidirectional"))
      (node (ref "R13") (pin "1") (pinfunction "1_1") (pintype "passive"))
      (node (ref "U$5") (pin "P$3") (pinfunction "3_P$3") (pintype "bidirectional"))
      (node (ref "U$5") (pin "P$4") (pinfunction "4_P$4") (pintype "bidirectional"))
    )
    (net (code "33") (name "MISO") (class "Default")
      (node (ref "IC1") (pin "2") (pinfunction "(PCINT14/MISO)PB6_2") (pintype "bidirectional"))
      (node (ref "ISP2") (pin "1") (pinfunction "MISO_1") (pintype "input"))
      (node (ref "J10") (pin "P$2") (pinfunction "2_P$2") (pintype "passive"))
      (node (ref "J2") (pin "4") (pinfunction "4_4") (pintype "passive"))
      (node (ref "U$2") (pin "7") (pinfunction "DATA_OUT_7") (pintype "output"))
      (node (ref "U3") (pin "2") (pinfunction "MISO_2") (pintype "bidirectional"))
    )
    (net (code "34") (name "MOSI") (class "Default")
      (node (ref "IC1") (pin "1") (pinfunction "(PCINT13/MOSI)PB5_1") (pintype "bidirectional"))
      (node (ref "ISP2") (pin "4") (pinfunction "MOSI_4") (pintype "output"))
      (node (ref "J10") (pin "P$3") (pinfunction "3_P$3") (pintype "passive"))
      (node (ref "J2") (pin "3") (pinfunction "3_3") (pintype "passive"))
      (node (ref "U$2") (pin "3") (pinfunction "DATA_IN_3") (pintype "input"))
      (node (ref "U3") (pin "3") (pinfunction "MOSI_3") (pintype "input"))
    )
    (net (code "35") (name "MUX_INT") (class "Default")
      (node (ref "IC1") (pin "33") (pinfunction "(PCINT4/ADC4)PA4_33") (pintype "bidirectional"))
      (node (ref "R12") (pin "1") (pinfunction "1_1") (pintype "passive"))
      (node (ref "U4") (pin "9") (pinfunction "~{INT}_9") (pintype "bidirectional"))
    )
    (net (code "36") (name "Net-(C12A-2)") (class "Default")
      (node (ref "C12") (pin "A2") (pinfunction "2_A2") (pintype "passive"))
      (node (ref "R27") (pin "1") (pinfunction "1_1") (pintype "passive"))
    )
    (net (code "37") (name "Net-(C12B-2)") (class "Default")
      (node (ref "C12") (pin "B2") (pinfunction "2_B2") (pintype "passive"))
      (node (ref "R28") (pin "1") (pinfunction "1_1") (pintype "passive"))
    )
    (net (code "38") (name "Net-(C29A-1)") (class "Default")
      (node (ref "C29") (pin "A1") (pinfunction "1_A1") (pintype "passive"))
      (node (ref "R26") (pin "1") (pinfunction "1_1") (pintype "passive"))
    )
    (net (code "39") (name "Net-(C29B-1)") (class "Default")
      (node (ref "C29") (pin "B1") (pinfunction "1_B1") (pintype "passive"))
      (node (ref "R19") (pin "1") (pinfunction "1_1") (pintype "passive"))
    )
    (net (code "40") (name "Net-(C29C-1)") (class "Default")
      (node (ref "C29") (pin "C1") (pinfunction "1_C1") (pintype "passive"))
      (node (ref "R18") (pin "1") (pinfunction "1_1") (pintype "passive"))
    )
    (net (code "41") (name "Net-(C29D-1)") (class "Default")
      (node (ref "C29") (pin "D1") (pinfunction "1_D1") (pintype "passive"))
      (node (ref "R15") (pin "1") (pinfunction "1_1") (pintype "passive"))
    )
    (net (code "42") (name "Net-(D1-PadA)") (class "Default")
      (node (ref "D1") (pin "A") (pinfunction "A_A") (pintype "passive"))
      (node (ref "R23") (pin "1") (pinfunction "1_1") (pintype "passive"))
    )
    (net (code "43") (name "Net-(D2-PadA)") (class "Default")
      (node (ref "D2") (pin "A") (pinfunction "A_A") (pintype "passive"))
      (node (ref "R24") (pin "1") (pinfunction "1_1") (pintype "passive"))
    )
    (net (code "44") (name "Net-(D3-PadA)") (class "Default")
      (node (ref "D3") (pin "A") (pinfunction "A_A") (pintype "passive"))
      (node (ref "R25") (pin "1") (pinfunction "1_1") (pintype "passive"))
    )
    (net (code "45") (name "Net-(IC1-XTAL1)") (class "Default")
      (node (ref "C25") (pin "2") (pinfunction "2_2") (pintype "passive"))
      (node (ref "IC1") (pin "8") (pinfunction "XTAL1_8") (pintype "bidirectional"))
      (node (ref "U$1") (pin "P$1") (pinfunction "1_P$1") (pintype "passive"))
    )
    (net (code "46") (name "Net-(IC1-XTAL2)") (class "Default")
      (node (ref "C24") (pin "2") (pinfunction "2_2") (pintype "passive"))
      (node (ref "IC1") (pin "7") (pinfunction "XTAL2_7") (pintype "bidirectional"))
      (node (ref "U$1") (pin "P$2") (pinfunction "2_P$2") (pintype "passive"))
    )
    (net (code "47") (name "Net-(LED1-PadA)") (class "Default")
      (node (ref "LED1") (pin "A") (pinfunction "A_A") (pintype "passive"))
      (node (ref "R5") (pin "2") (pinfunction "2_2") (pintype "passive"))
    )
    (net (code "48") (name "Net-(LED2-PadA)") (class "Default")
      (node (ref "LED2") (pin "A") (pinfunction "A_A") (pintype "passive"))
      (node (ref "R4") (pin "2") (pinfunction "2_2") (pintype "passive"))
    )
    (net (code "49") (name "Net-(MICRO_USB-D+)") (class "Default")
      (node (ref "CX3") (pin "2") (pinfunction "2_2") (pintype "passive"))
      (node (ref "D+") (pin "2") (pinfunction "2_2") (pintype "passive"))
      (node (ref "MICRO_USB") (pin "3") (pinfunction "D+_3") (pintype "bidirectional"))
    )
    (net (code "50") (name "Net-(MICRO_USB-D-)") (class "Default")
      (node (ref "CX2") (pin "2") (pinfunction "2_2") (pintype "passive"))
      (node (ref "D-") (pin "2") (pinfunction "2_2") (pintype "passive"))
      (node (ref "MICRO_USB") (pin "2") (pinfunction "D-_2") (pintype "bidirectional"))
    )
    (net (code "51") (name "Net-(Q1-D)") (class "Default")
      (node (ref "Q1") (pin "3") (pinfunction "D_3") (pintype "bidirectional"))
      (node (ref "Q6") (pin "1") (pinfunction "G_1") (pintype "bidirectional"))
      (node (ref "R21") (pin "2") (pinfunction "2_2") (pintype "passive"))
    )
    (net (code "52") (name "Net-(Q5-D)") (class "Default")
      (node (ref "F1") (pin "1") (pinfunction "1_1") (pintype "bidirectional"))
      (node (ref "Q5") (pin "3") (pinfunction "D_3") (pintype "bidirectional"))
    )
    (net (code "53") (name "Net-(Q6-D)") (class "Default")
      (node (ref "F2") (pin "1") (pinfunction "1_1") (pintype "bidirectional"))
      (node (ref "Q6") (pin "3") (pinfunction "D_3") (pintype "bidirectional"))
    )
    (net (code "54") (name "Net-(RTC1-VBAT)") (class "Default")
      (node (ref "BT1") (pin "POWER0") (pinfunction "+_POWER0") (pintype "passive"))
      (node (ref "BT1") (pin "POWER1") (pinfunction "+_POWER1") (pintype "passive"))
      (node (ref "RTC1") (pin "6") (pinfunction "VBAT_6") (pintype "power_in"))
    )
    (net (code "55") (name "Net-(U$3-FB)") (class "Default")
      (node (ref "C11") (pin "1") (pinfunction "1_1") (pintype "passive"))
      (node (ref "R1") (pin "2") (pinfunction "2_2") (pintype "passive"))
      (node (ref "R2") (pin "1") (pinfunction "1_1") (pintype "passive"))
      (node (ref "U$3") (pin "P$8") (pinfunction "FB_P$8") (pintype "input"))
    )
    (net (code "56") (name "Net-(U$3-L1)") (class "Default")
      (node (ref "U$3") (pin "P$1") (pinfunction "L1_P$1") (pintype "input"))
      (node (ref "U$8") (pin "P$1") (pinfunction "1_P$1") (pintype "passive"))
    )
    (net (code "57") (name "Net-(U$3-L2)") (class "Default")
      (node (ref "U$3") (pin "P$10") (pinfunction "L2_P$10") (pintype "input"))
      (node (ref "U$8") (pin "P$2") (pinfunction "2_P$2") (pintype "passive"))
    )
    (net (code "58") (name "Net-(U$3-VAUX)") (class "Default")
      (node (ref "C1") (pin "1") (pinfunction "1_1") (pintype "passive"))
      (node (ref "U$3") (pin "P$6") (pinfunction "VAUX_P$6") (pintype "input"))
    )
    (net (code "59") (name "Net-(U$4-SW)") (class "Default")
      (node (ref "L2") (pin "P$1") (pinfunction "P$1_P$1") (pintype "bidirectional"))
      (node (ref "U$4") (pin "P$9") (pinfunction "SW_P$9") (pintype "bidirectional"))
    )
    (net (code "60") (name "Net-(U$6-SCL)") (class "Default")
      (node (ref "R17") (pin "1") (pinfunction "1_1") (pintype "passive"))
      (node (ref "U$6") (pin "12") (pinfunction "SCL_12") (pintype "bidirectional"))
    )
    (net (code "61") (name "Net-(U$6-SDA)") (class "Default")
      (node (ref "R16") (pin "1") (pinfunction "1_1") (pintype "passive"))
      (node (ref "U$6") (pin "9") (pinfunction "SDA_9") (pintype "bidirectional"))
    )
    (net (code "62") (name "Net-(U$7-ADCINN)") (class "Default")
      (node (ref "U$7") (pin "26") (pinfunction "ADCINN_26") (pintype "bidirectional"))
      (node (ref "U$7") (pin "27") (pinfunction "MUXOUTN_27") (pintype "bidirectional"))
    )
    (net (code "63") (name "Net-(U$7-ADCINP)") (class "Default")
      (node (ref "U$7") (pin "24") (pinfunction "MUXOUTP_24") (pintype "bidirectional"))
      (node (ref "U$7") (pin "25") (pinfunction "ADCINP_25") (pintype "bidirectional"))
    )
    (net (code "64") (name "Net-(U$7-CH14)") (class "Default")
      (node (ref "R46") (pin "1") (pinfunction "1_1") (pintype "passive"))
      (node (ref "R47") (pin "1") (pinfunction "1_1") (pintype "passive"))
      (node (ref "U$7") (pin "22") (pinfunction "CH14_22") (pintype "input"))
    )
    (net (code "65") (name "Net-(U$10-FILT)") (class "Default")
      (node (ref "C22") (pin "1") (pinfunction "1_1") (pintype "passive"))
      (node (ref "U$10") (pin "1") (pinfunction "FILT_1") (pintype "bidirectional"))
    )
    (net (code "66") (name "Net-(U$10-OUTF)") (class "Default")
      (node (ref "C23") (pin "1") (pinfunction "1_1") (pintype "passive"))
      (node (ref "U$10") (pin "5") (pinfunction "OUTS_5") (pintype "bidirectional"))
      (node (ref "U$10") (pin "6") (pinfunction "OUTF_6") (pintype "bidirectional"))
      (node (ref "U$7") (pin "23") (pinfunction "CH15_23") (pintype "input"))
    )
    (net (code "67") (name "Net-(U2-3V3OUT)") (class "Default")
      (node (ref "C14") (pin "1") (pinfunction "1_1") (pintype "passive"))
      (node (ref "U2") (pin "10") (pinfunction "3V3OUT_10") (pintype "bidirectional"))
      (node (ref "U2") (pin "11") (pinfunction "RESET#_11") (pintype "bidirectional"))
      (node (ref "U2") (pin "20") (pinfunction "VCCIO_20") (pintype "bidirectional"))
    )
    (net (code "68") (name "Net-(U2-CBUS1)") (class "Default")
      (node (ref "LED1") (pin "C") (pinfunction "C_C") (pintype "passive"))
      (node (ref "U2") (pin "14") (pinfunction "CBUS1_14") (pintype "bidirectional"))
    )
    (net (code "69") (name "Net-(U2-CBUS2)") (class "Default")
      (node (ref "LED2") (pin "C") (pinfunction "C_C") (pintype "passive"))
      (node (ref "U2") (pin "7") (pinfunction "CBUS2_7") (pintype "bidirectional"))
    )
    (net (code "70") (name "Net-(U2-RXD)") (class "Default")
      (node (ref "R7") (pin "2") (pinfunction "2_2") (pintype "passive"))
      (node (ref "U2") (pin "1") (pinfunction "RXD_1") (pintype "bidirectional"))
    )
    (net (code "71") (name "Net-(U2-TXD)") (class "Default")
      (node (ref "R10") (pin "2") (pinfunction "2_2") (pintype "passive"))
      (node (ref "U2") (pin "17") (pinfunction "TXD_17") (pintype "bidirectional"))
    )
    (net (code "72") (name "Net-(U2-USBDM)") (class "Default")
      (node (ref "D-") (pin "1") (pinfunction "1_1") (pintype "passive"))
      (node (ref "U2") (pin "9") (pinfunction "USBDM_9") (pintype "bidirectional"))
    )
    (net (code "73") (name "Net-(U2-USBDP)") (class "Default")
      (node (ref "D+") (pin "1") (pinfunction "1_1") (pintype "passive"))
      (node (ref "U2") (pin "8") (pinfunction "USBDP_8") (pintype "bidirectional"))
    )
    (net (code "74") (name "Net-(U3-ANT)") (class "Default")
      (node (ref "U3") (pin "9") (pinfunction "ANT_9") (pintype "passive"))
      (node (ref "X1") (pin "P") (pinfunction "ANT_P") (pintype "bidirectional"))
    )
    (net (code "75") (name "Net-(U4-~{RESET})") (class "Default")
      (node (ref "R11") (pin "1") (pinfunction "1_1") (pintype "passive"))
      (node (ref "U4") (pin "23") (pinfunction "~{RESET}_23") (pintype "bidirectional"))
    )
    (net (code "76") (name "RADIO_CS") (class "Default")
      (node (ref "IC1") (pin "26") (pinfunction "(PCINT23/TOSC2)PC7_26") (pintype "output"))
      (node (ref "U3") (pin "5") (pinfunction "NSS_5") (pintype "input"))
    )
    (net (code "77") (name "RADIO_INT") (class "Default")
      (node (ref "IC1") (pin "32") (pinfunction "(PCINT5/ADC5)PA5_32") (pintype "bidirectional"))
      (node (ref "U3") (pin "14") (pinfunction "DIO0_14") (pintype "bidirectional"))
    )
    (net (code "78") (name "REF_CTRL") (class "Default")
      (node (ref "U$10") (pin "3") (pinfunction "EN_3") (pintype "bidirectional"))
      (node (ref "U4") (pin "2") (pinfunction "I/O[3]_2") (pintype "bidirectional"))
    )
    (net (code "79") (name "RST") (class "Default")
      (node (ref "IC1") (pin "4") (pinfunction "RESET_4") (pintype "input"))
      (node (ref "ISP2") (pin "5") (pinfunction "RST_5") (pintype "output"))
      (node (ref "R3") (pin "1") (pinfunction "1_1") (pintype "passive"))
      (node (ref "U$9") (pin "P$3") (pinfunction "3_P$3") (pintype "bidirectional"))
      (node (ref "U$9") (pin "P$4") (pinfunction "4_P$4") (pintype "bidirectional"))
    )
    (net (code "80") (name "RTC_INT") (class "Default")
      (node (ref "IC1") (pin "31") (pinfunction "(PCINT6/ADC6)PA6_31") (pintype "bidirectional"))
      (node (ref "RTC1") (pin "3") (pinfunction "SQW_3") (pintype "output"))
    )
    (net (code "81") (name "RX") (class "Default")
      (node (ref "IC1") (pin "9") (pinfunction "(PCINT24/RXD0)PD0_9") (pintype "bidirectional"))
      (node (ref "R10") (pin "1") (pinfunction "1_1") (pintype "passive"))
    )
    (net (code "82") (name "RX_EXT") (class "Default")
      (node (ref "IC1") (pin "11") (pinfunction "(PCINT26/INT0)PD2_11") (pintype "bidirectional"))
      (node (ref "J9") (pin "P$7") (pinfunction "7_P$7") (pintype "passive"))
    )
    (net (code "83") (name "SCK") (class "Default")
      (node (ref "IC1") (pin "3") (pinfunction "(PCINT15/SCK)PB7_3") (pintype "bidirectional"))
      (node (ref "ISP2") (pin "3") (pinfunction "SCK_3") (pintype "output"))
      (node (ref "J10") (pin "P$4") (pinfunction "4_P$4") (pintype "passive"))
      (node (ref "J2") (pin "5") (pinfunction "5_5") (pintype "passive"))
      (node (ref "U$2") (pin "5") (pinfunction "SCLK_5") (pintype "input"))
      (node (ref "U3") (pin "4") (pinfunction "SCK_4") (pintype "input"))
    )
    (net (code "84") (name "SCL") (class "Default")
      (node (ref "IC1") (pin "19") (pinfunction "(PCINT16/SCL)PC0_19") (pintype "output"))
      (node (ref "J1") (pin "4") (pinfunction "4_4") (pintype "passive"))
      (node (ref "J9") (pin "P$10") (pinfunction "10_P$10") (pintype "passive"))
      (node (ref "Q9") (pin "2") (pinfunction "S_2") (pintype "bidirectional"))
      (node (ref "R17") (pin "2") (pinfunction "2_2") (pintype "passive"))
      (node (ref "R42") (pin "1") (pinfunction "1_1") (pintype "passive"))
      (node (ref "RTC1") (pin "8") (pinfunction "SCL_8") (pintype "bidirectional"))
      (node (ref "U4") (pin "25") (pinfunction "SCL_25") (pintype "bidirectional"))
    )
    (net (code "85") (name "SCL_HV") (class "Default")
      (node (ref "Q9") (pin "3") (pinfunction "D_3") (pintype "bidirectional"))
      (node (ref "R9") (pin "1") (pinfunction "1_1") (pintype "passive"))
      (node (ref "U$7") (pin "2") (pinfunction "SCL_2") (pintype "bidirectional"))
    )
    (net (code "86") (name "SDA") (class "Default")
      (node (ref "IC1") (pin "20") (pinfunction "(PCINT17/SDA)PC1_20") (pintype "output"))
      (node (ref "J1") (pin "3") (pinfunction "3_3") (pintype "passive"))
      (node (ref "J9") (pin "P$9") (pinfunction "9_P$9") (pintype "passive"))
      (node (ref "Q8") (pin "2") (pinfunction "S_2") (pintype "bidirectional"))
      (node (ref "R16") (pin "2") (pinfunction "2_2") (pintype "passive"))
      (node (ref "R43") (pin "1") (pinfunction "1_1") (pintype "passive"))
      (node (ref "RTC1") (pin "7") (pinfunction "SDA_7") (pintype "bidirectional"))
      (node (ref "U4") (pin "24") (pinfunction "SDA_24") (pintype "bidirectional"))
    )
    (net (code "87") (name "SDA_HV") (class "Default")
      (node (ref "Q8") (pin "3") (pinfunction "D_3") (pintype "bidirectional"))
      (node (ref "R8") (pin "1") (pinfunction "1_1") (pintype "passive"))
      (node (ref "U$7") (pin "3") (pinfunction "SDA_3") (pintype "bidirectional"))
    )
    (net (code "88") (name "SD_CD") (class "Default")
      (node (ref "U$2") (pin "CD1") (pinfunction "CARD_DETECT_CD1") (pintype "passive"))
    )
    (net (code "89") (name "SD_CS") (class "Default")
      (node (ref "IC1") (pin "13") (pinfunction "(PCINT28/OC1B)PD4_13") (pintype "bidirectional"))
      (node (ref "U$2") (pin "2") (pinfunction "CS_2") (pintype "input"))
    )
    (net (code "90") (name "SD_VCC") (class "Default")
      (node (ref "Q7") (pin "3") (pinfunction "D_3") (pintype "bidirectional"))
      (node (ref "U$2") (pin "4") (pinfunction "VDD_4") (pintype "power_in"))
    )
    (net (code "91") (name "SD_VCC_CTRL") (class "Default")
      (node (ref "Q7") (pin "1") (pinfunction "G_1") (pintype "bidirectional"))
      (node (ref "R22") (pin "2") (pinfunction "2_2") (pintype "passive"))
      (node (ref "U4") (pin "1") (pinfunction "I/O[2]_1") (pintype "bidirectional"))
    )
    (net (code "92") (name "SPI_EXT_CS1") (class "Default")
      (node (ref "J2") (pin "6") (pinfunction "6_6") (pintype "passive"))
      (node (ref "U4") (pin "16") (pinfunction "I/O[11]_16") (pintype "bidirectional"))
    )
    (net (code "93") (name "SPI_EXT_CS2") (class "Default")
      (node (ref "J10") (pin "P$6") (pinfunction "6_P$6") (pintype "passive"))
      (node (ref "U4") (pin "14") (pinfunction "I/O[9]_14") (pintype "bidirectional"))
    )
    (net (code "94") (name "SS") (class "Default")
      (node (ref "IC1") (pin "44") (pinfunction "(PCINT12/OC0B/~{SS})PB4_44") (pintype "bidirectional"))
    )
    (net (code "95") (name "TX") (class "Default")
      (node (ref "IC1") (pin "10") (pinfunction "(PCINT25/TXD0)PD1_10") (pintype "bidirectional"))
      (node (ref "R7") (pin "1") (pinfunction "1_1") (pintype "passive"))
    )
    (net (code "96") (name "TX_EXT") (class "Default")
      (node (ref "IC1") (pin "12") (pinfunction "(PCINT27/INT1)PD3_12") (pintype "bidirectional"))
      (node (ref "J9") (pin "P$8") (pinfunction "8_P$8") (pintype "passive"))
    )
    (net (code "97") (name "VUSB") (class "Default")
      (node (ref "C13") (pin "A") (pinfunction "+_A") (pintype "passive"))
      (node (ref "C17") (pin "1") (pinfunction "1_1") (pintype "passive"))
      (node (ref "MICRO_USB") (pin "1") (pinfunction "VDD_1") (pintype "power_in"))
      (node (ref "R4") (pin "1") (pinfunction "1_1") (pintype "passive"))
      (node (ref "R5") (pin "1") (pinfunction "1_1") (pintype "passive"))
      (node (ref "U2") (pin "12") (pinfunction "VCC_12") (pintype "bidirectional"))
    )
    (net (code "98") (name "unconnected-(C12C-1-PadC1)") (class "Default")
      (node (ref "C12") (pin "C1") (pinfunction "1_C1") (pintype "passive"))
    )
    (net (code "99") (name "unconnected-(C12C-2-PadC2)") (class "Default")
      (node (ref "C12") (pin "C2") (pinfunction "2_C2") (pintype "passive"))
    )
    (net (code "100") (name "unconnected-(C12D-1-PadD1)") (class "Default")
      (node (ref "C12") (pin "D1") (pinfunction "1_D1") (pintype "passive"))
    )
    (net (code "101") (name "unconnected-(C12D-2-PadD2)") (class "Default")
      (node (ref "C12") (pin "D2") (pinfunction "2_D2") (pintype "passive"))
    )
    (net (code "102") (name "unconnected-(IC1-(PCINT0{slash}ADC0)PA0-Pad37)") (class "Default")
      (node (ref "IC1") (pin "37") (pinfunction "(PCINT0/ADC0)PA0_37") (pintype "bidirectional"))
    )
    (net (code "103") (name "unconnected-(IC1-(PCINT1{slash}ADC1)PA1-Pad36)") (class "Default")
      (node (ref "IC1") (pin "36") (pinfunction "(PCINT1/ADC1)PA1_36") (pintype "bidirectional"))
    )
    (net (code "104") (name "unconnected-(IC1-(PCINT2{slash}ADC2)PA2-Pad35)") (class "Default")
      (node (ref "IC1") (pin "35") (pinfunction "(PCINT2/ADC2)PA2_35") (pintype "bidirectional"))
    )
    (net (code "105") (name "unconnected-(IC1-(PCINT8{slash}XCK0{slash}T0)PB0-Pad40)") (class "Default")
      (node (ref "IC1") (pin "40") (pinfunction "(PCINT8/XCK0/T0)PB0_40") (pintype "bidirectional"))
    )
    (net (code "106") (name "unconnected-(IC1-(PCINT9{slash}CLKO{slash}T1)PB1-Pad41)") (class "Default")
      (node (ref "IC1") (pin "41") (pinfunction "(PCINT9/CLKO/T1)PB1_41") (pintype "bidirectional"))
    )
    (net (code "107") (name "unconnected-(IC1-(PCINT10{slash}INT2{slash}AIN0)PB2-Pad42)") (class "Default")
      (node (ref "IC1") (pin "42") (pinfunction "(PCINT10/INT2/AIN0)PB2_42") (pintype "bidirectional"))
    )
    (net (code "108") (name "unconnected-(IC1-(PCINT11{slash}OC0A{slash}AIN1)PB3-Pad43)") (class "Default")
      (node (ref "IC1") (pin "43") (pinfunction "(PCINT11/OC0A/AIN1)PB3_43") (pintype "bidirectional"))
    )
    (net (code "109") (name "unconnected-(IC1-(PCINT18{slash}TCK)PC2-Pad21)") (class "Default")
      (node (ref "IC1") (pin "21") (pinfunction "(PCINT18/TCK)PC2_21") (pintype "output"))
    )
    (net (code "110") (name "unconnected-(IC1-(PCINT19{slash}TMS)PC3-Pad22)") (class "Default")
      (node (ref "IC1") (pin "22") (pinfunction "(PCINT19/TMS)PC3_22") (pintype "output"))
    )
    (net (code "111") (name "unconnected-(IC1-(PCINT20{slash}TDO)PC4-Pad23)") (class "Default")
      (node (ref "IC1") (pin "23") (pinfunction "(PCINT20/TDO)PC4_23") (pintype "output"))
    )
    (net (code "112") (name "unconnected-(IC1-(PCINT21{slash}TDI)PC5-Pad24)") (class "Default")
      (node (ref "IC1") (pin "24") (pinfunction "(PCINT21/TDI)PC5_24") (pintype "output"))
    )
    (net (code "113") (name "unconnected-(IC1-(PCINT29{slash}OC1A)PD5-Pad14)") (class "Default")
      (node (ref "IC1") (pin "14") (pinfunction "(PCINT29/OC1A)PD5_14") (pintype "bidirectional"))
    )
    (net (code "114") (name "unconnected-(IC1-(PCINT30{slash}OC2B{slash}ICP)PD6-Pad15)") (class "Default")
      (node (ref "IC1") (pin "15") (pinfunction "(PCINT30/OC2B/ICP)PD6_15") (pintype "bidirectional"))
    )
    (net (code "115") (name "unconnected-(IC1-(PCINT31{slash}OC2A)PD7-Pad16)") (class "Default")
      (node (ref "IC1") (pin "16") (pinfunction "(PCINT31/OC2A)PD7_16") (pintype "bidirectional"))
    )
    (net (code "116") (name "unconnected-(J4-PAD1-PadNC1)") (class "Default")
      (node (ref "J4") (pin "NC1") (pinfunction "PAD1_NC1") (pintype "bidirectional"))
    )
    (net (code "117") (name "unconnected-(J4-PAD2-PadNC2)") (class "Default")
      (node (ref "J4") (pin "NC2") (pinfunction "PAD2_NC2") (pintype "bidirectional"))
    )
    (net (code "118") (name "unconnected-(MICRO_USB-ID-Pad4)") (class "Default")
      (node (ref "MICRO_USB") (pin "4") (pinfunction "ID_4") (pintype "passive"))
    )
    (net (code "119") (name "unconnected-(RTC1-32KHZ-Pad1)") (class "Default")
      (node (ref "RTC1") (pin "1") (pinfunction "32KHZ_1") (pintype "output"))
    )
    (net (code "120") (name "unconnected-(RTC1-RST-Pad4)") (class "Default")
      (node (ref "RTC1") (pin "4") (pinfunction "RST_4") (pintype "bidirectional"))
    )
    (net (code "121") (name "unconnected-(U$2-CARD_DETECT1-PadCD2)") (class "Default")
      (node (ref "U$2") (pin "CD2") (pinfunction "CARD_DETECT1_CD2") (pintype "passive"))
    )
    (net (code "122") (name "unconnected-(U$2-DAT1-Pad8)") (class "Default")
      (node (ref "U$2") (pin "8") (pinfunction "DAT1_8") (pintype "bidirectional"))
    )
    (net (code "123") (name "unconnected-(U$2-DAT2-Pad1)") (class "Default")
      (node (ref "U$2") (pin "1") (pinfunction "DAT2_1") (pintype "bidirectional"))
    )
    (net (code "124") (name "unconnected-(U$3-PG-PadP$5)") (class "Default")
      (node (ref "U$3") (pin "P$5") (pinfunction "PG_P$5") (pintype "input"))
    )
    (net (code "125") (name "unconnected-(U$4-PG-PadP$7)") (class "Default")
      (node (ref "U$4") (pin "P$7") (pinfunction "PG_P$7") (pintype "bidirectional"))
    )
    (net (code "126") (name "unconnected-(U$6-EXTINT0-Pad19)") (class "Default")
      (node (ref "U$6") (pin "19") (pinfunction "EXTINT0_19") (pintype "bidirectional"))
    )
    (net (code "127") (name "unconnected-(U$6-RESET_N-Pad18)") (class "Default")
      (node (ref "U$6") (pin "18") (pinfunction "RESET_N_18") (pintype "bidirectional"))
    )
    (net (code "128") (name "unconnected-(U$6-RXD-Pad14)") (class "Default")
      (node (ref "U$6") (pin "14") (pinfunction "RXD_14") (pintype "bidirectional"))
    )
    (net (code "129") (name "unconnected-(U$6-SAFEBOOT_N-Pad8)") (class "Default")
      (node (ref "U$6") (pin "8") (pinfunction "SAFEBOOT_N_8") (pintype "bidirectional"))
    )
    (net (code "130") (name "unconnected-(U$6-TIMEPULSE-Pad7)") (class "Default")
      (node (ref "U$6") (pin "7") (pinfunction "TIMEPULSE_7") (pintype "bidirectional"))
    )
    (net (code "131") (name "unconnected-(U$6-TXD-Pad13)") (class "Default")
      (node (ref "U$6") (pin "13") (pinfunction "TXD_13") (pintype "bidirectional"))
    )
    (net (code "132") (name "unconnected-(U$7-CA0-Pad36)") (class "Default")
      (node (ref "U$7") (pin "36") (pinfunction "CA0_36") (pintype "input"))
    )
    (net (code "133") (name "unconnected-(U$7-CA1-Pad37)") (class "Default")
      (node (ref "U$7") (pin "37") (pinfunction "CA1_37") (pintype "input"))
    )
    (net (code "134") (name "unconnected-(U$7-CA2-Pad38)") (class "Default")
      (node (ref "U$7") (pin "38") (pinfunction "CA2_38") (pintype "input"))
    )
    (net (code "135") (name "unconnected-(U$7-CH12-Pad20)") (class "Default")
      (node (ref "U$7") (pin "20") (pinfunction "CH12_20") (pintype "input"))
    )
    (net (code "136") (name "unconnected-(U$7-CH13-Pad21)") (class "Default")
      (node (ref "U$7") (pin "21") (pinfunction "CH13_21") (pintype "input"))
    )
    (net (code "137") (name "unconnected-(U$7-F0-Pad35)") (class "Default")
      (node (ref "U$7") (pin "35") (pinfunction "F0_35") (pintype "input"))
    )
    (net (code "138") (name "unconnected-(U$15-BUSY-Pad15)") (class "Default")
      (node (ref "U$15") (pin "15") (pinfunction "BUSY_15") (pintype "bidirectional"))
    )
    (net (code "139") (name "unconnected-(U$15-F0-Pad14)") (class "Default")
      (node (ref "U$15") (pin "14") (pinfunction "F0_14") (pintype "bidirectional"))
    )
    (net (code "140") (name "unconnected-(U$15-GND-Pad1)") (class "Default")
      (node (ref "U$15") (pin "1") (pinfunction "GND_1") (pintype "bidirectional"))
    )
    (net (code "141") (name "unconnected-(U$15-GND-Pad8)") (class "Default")
      (node (ref "U$15") (pin "8") (pinfunction "GND_8") (pintype "bidirectional"))
    )
    (net (code "142") (name "unconnected-(U$15-GND-Pad9)") (class "Default")
      (node (ref "U$15") (pin "9") (pinfunction "GND_9") (pintype "bidirectional"))
    )
    (net (code "143") (name "unconnected-(U$15-GND-Pad16)") (class "Default")
      (node (ref "U$15") (pin "16") (pinfunction "GND_16") (pintype "bidirectional"))
    )
    (net (code "144") (name "unconnected-(U$15-IN+-Pad5)") (class "Default")
      (node (ref "U$15") (pin "5") (pinfunction "IN+_5") (pintype "bidirectional"))
    )
    (net (code "145") (name "unconnected-(U$15-IN--Pad6)") (class "Default")
      (node (ref "U$15") (pin "6") (pinfunction "IN-_6") (pintype "bidirectional"))
    )
    (net (code "146") (name "unconnected-(U$15-REF+-Pad3)") (class "Default")
      (node (ref "U$15") (pin "3") (pinfunction "REF+_3") (pintype "bidirectional"))
    )
    (net (code "147") (name "unconnected-(U$15-REF--Pad4)") (class "Default")
      (node (ref "U$15") (pin "4") (pinfunction "REF-_4") (pintype "bidirectional"))
    )
    (net (code "148") (name "unconnected-(U$15-SCK-Pad13)") (class "Default")
      (node (ref "U$15") (pin "13") (pinfunction "SCK_13") (pintype "bidirectional"))
    )
    (net (code "149") (name "unconnected-(U$15-SDI-Pad7)") (class "Default")
      (node (ref "U$15") (pin "7") (pinfunction "SDI_7") (pintype "bidirectional"))
    )
    (net (code "150") (name "unconnected-(U$15-SDO-Pad12)") (class "Default")
      (node (ref "U$15") (pin "12") (pinfunction "SDO_12") (pintype "bidirectional"))
    )
    (net (code "151") (name "unconnected-(U$15-VCC-Pad2)") (class "Default")
      (node (ref "U$15") (pin "2") (pinfunction "VCC_2") (pintype "bidirectional"))
    )
    (net (code "152") (name "unconnected-(U$15-{slash}CS-Pad11)") (class "Default")
      (node (ref "U$15") (pin "11") (pinfunction "/CS_11") (pintype "bidirectional"))
    )
    (net (code "153") (name "unconnected-(U$15-{slash}EXT-Pad10)") (class "Default")
      (node (ref "U$15") (pin "10") (pinfunction "/EXT_10") (pintype "bidirectional"))
    )
    (net (code "154") (name "unconnected-(U2-CBUS0-Pad15)") (class "Default")
      (node (ref "U2") (pin "15") (pinfunction "CBUS0_15") (pintype "bidirectional"))
    )
    (net (code "155") (name "unconnected-(U2-CBUS3-Pad16)") (class "Default")
      (node (ref "U2") (pin "16") (pinfunction "CBUS3_16") (pintype "bidirectional"))
    )
    (net (code "156") (name "unconnected-(U2-DCD#-Pad5)") (class "Default")
      (node (ref "U2") (pin "5") (pinfunction "DCD#_5") (pintype "bidirectional"))
    )
    (net (code "157") (name "unconnected-(U2-DSR#-Pad4)") (class "Default")
      (node (ref "U2") (pin "4") (pinfunction "DSR#_4") (pintype "bidirectional"))
    )
    (net (code "158") (name "unconnected-(U2-RI#-Pad2)") (class "Default")
      (node (ref "U2") (pin "2") (pinfunction "RI#_2") (pintype "bidirectional"))
    )
    (net (code "159") (name "unconnected-(U2-RTS#-Pad19)") (class "Default")
      (node (ref "U2") (pin "19") (pinfunction "RTS#_19") (pintype "bidirectional"))
    )
    (net (code "160") (name "unconnected-(U3-DIO1-Pad15)") (class "Default")
      (node (ref "U3") (pin "15") (pinfunction "DIO1_15") (pintype "bidirectional"))
    )
    (net (code "161") (name "unconnected-(U3-DIO2-Pad16)") (class "Default")
      (node (ref "U3") (pin "16") (pinfunction "DIO2_16") (pintype "bidirectional"))
    )
    (net (code "162") (name "unconnected-(U3-DIO3-Pad11)") (class "Default")
      (node (ref "U3") (pin "11") (pinfunction "DIO3_11") (pintype "bidirectional"))
    )
    (net (code "163") (name "unconnected-(U3-DIO4-Pad12)") (class "Default")
      (node (ref "U3") (pin "12") (pinfunction "DIO4_12") (pintype "bidirectional"))
    )
    (net (code "164") (name "unconnected-(U3-DIO5-Pad7)") (class "Default")
      (node (ref "U3") (pin "7") (pinfunction "DIO5_7") (pintype "bidirectional"))
    )
    (net (code "165") (name "unconnected-(U3-RESET-Pad6)") (class "Default")
      (node (ref "U3") (pin "6") (pinfunction "RESET_6") (pintype "input"))
    )
    (net (code "166") (name "unconnected-(U4-I{slash}O[0]-Pad27)") (class "Default")
      (node (ref "U4") (pin "27") (pinfunction "I/O[0]_27") (pintype "bidirectional"))
    )
    (net (code "167") (name "unconnected-(U4-I{slash}O[1]-Pad28)") (class "Default")
      (node (ref "U4") (pin "28") (pinfunction "I/O[1]_28") (pintype "bidirectional"))
    )
    (net (code "168") (name "unconnected-(U4-OSCIO-Pad11)") (class "Default")
      (node (ref "U4") (pin "11") (pinfunction "OSCIO_11") (pintype "bidirectional"))
    )
  )
)
